# RPi-HAT_Conn-EE.net
KiCad netlist of a schematic drawn in Altium Designer
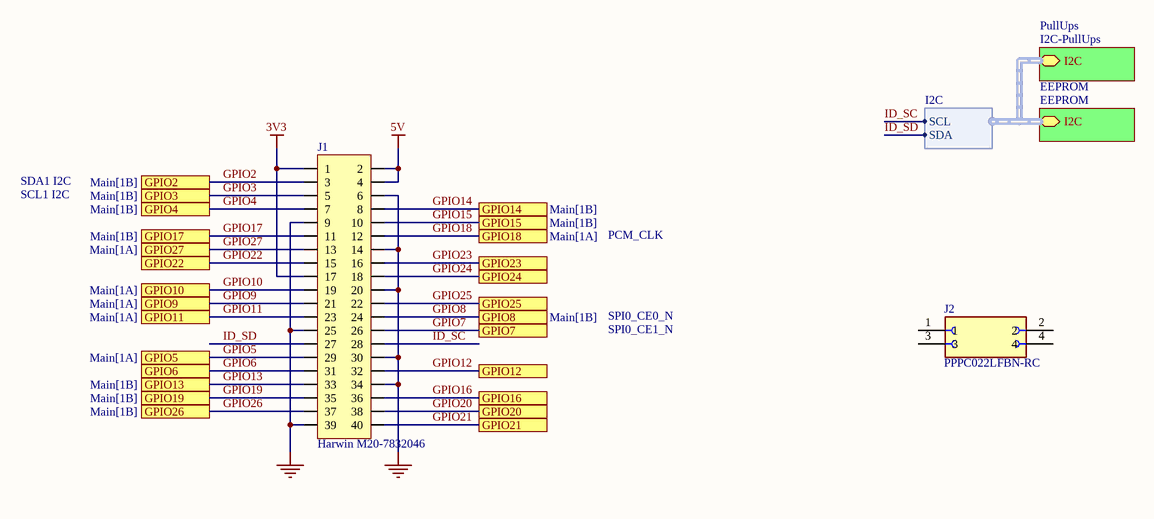
[diagram p0: RPi-HAT_Conn-EE.SchDoc]

(export (version "E")
  (design (tool "Eeschema 10.0.6"))
  (components
    (comp (ref "J1")
      (value "Harwin M20-7832046")
      (footprint "PCB-677180-1")
      (description "Headers & Wire Housings 20+20 DIL VERTICAL SOCKET TIN")
      (libsource (lib "CommunityVault") (part "CMP-2482621-3"))
    )
    (comp (ref "J2")
      (value "PPPC022LFBN-RC")
      (footprint "SULLINS_PPPC022LFBN-RC")
      (description "4 Position Header Connector 0.100 (2.54mm) Through Hole Gold")
      (fields (field (name "MF") "Sullins Connector Solutions"))
      (libsource (lib "Twill Technology Inc") (part "PPPC022LFBN-RC"))
    )
  )
  (nets
    (net (code "2") (name "/GPIO2") (class "Default")
      (node (ref "J1") (pin "3") (pinfunction "3_3") (pintype "passive"))
    )
    (net (code "3") (name "/GPIO3") (class "Default")
      (node (ref "J1") (pin "5") (pinfunction "5_5") (pintype "passive"))
    )
    (net (code "4") (name "/GPIO4") (class "Default")
      (node (ref "J1") (pin "7") (pinfunction "7_7") (pintype "passive"))
    )
    (net (code "5") (name "/GPIO5") (class "Default")
      (node (ref "J1") (pin "29") (pinfunction "29_29") (pintype "passive"))
    )
    (net (code "6") (name "/GPIO6") (class "Default")
      (node (ref "J1") (pin "31") (pinfunction "31_31") (pintype "passive"))
    )
    (net (code "7") (name "/GPIO7") (class "Default")
      (node (ref "J1") (pin "26") (pinfunction "26_26") (pintype "passive"))
    )
    (net (code "8") (name "/GPIO8") (class "Default")
      (node (ref "J1") (pin "24") (pinfunction "24_24") (pintype "passive"))
    )
    (net (code "9") (name "/GPIO9") (class "Default")
      (node (ref "J1") (pin "21") (pinfunction "21_21") (pintype "passive"))
    )
    (net (code "10") (name "/GPIO10") (class "Default")
      (node (ref "J1") (pin "19") (pinfunction "19_19") (pintype "passive"))
    )
    (net (code "11") (name "/GPIO11") (class "Default")
      (node (ref "J1") (pin "23") (pinfunction "23_23") (pintype "passive"))
    )
    (net (code "12") (name "/GPIO12") (class "Default")
      (node (ref "J1") (pin "32") (pinfunction "32_32") (pintype "passive"))
    )
    (net (code "13") (name "/GPIO13") (class "Default")
      (node (ref "J1") (pin "33") (pinfunction "33_33") (pintype "passive"))
    )
    (net (code "14") (name "/GPIO14") (class "Default")
      (node (ref "J1") (pin "8") (pinfunction "8_8") (pintype "passive"))
    )
    (net (code "15") (name "/GPIO15") (class "Default")
      (node (ref "J1") (pin "10") (pinfunction "10_10") (pintype "passive"))
    )
    (net (code "16") (name "/GPIO16") (class "Default")
      (node (ref "J1") (pin "36") (pinfunction "36_36") (pintype "passive"))
    )
    (net (code "17") (name "/GPIO17") (class "Default")
      (node (ref "J1") (pin "11") (pinfunction "11_11") (pintype "passive"))
    )
    (net (code "18") (name "/GPIO18") (class "Default")
      (node (ref "J1") (pin "12") (pinfunction "12_12") (pintype "passive"))
    )
    (net (code "19") (name "/GPIO19") (class "Default")
      (node (ref "J1") (pin "35") (pinfunction "35_35") (pintype "passive"))
    )
    (net (code "20") (name "/GPIO20") (class "Default")
      (node (ref "J1") (pin "38") (pinfunction "38_38") (pintype "passive"))
    )
    (net (code "21") (name "/GPIO21") (class "Default")
      (node (ref "J1") (pin "40") (pinfunction "40_40") (pintype "passive"))
    )
    (net (code "22") (name "/GPIO22") (class "Default")
      (node (ref "J1") (pin "15") (pinfunction "15_15") (pintype "passive"))
    )
    (net (code "23") (name "/GPIO23") (class "Default")
      (node (ref "J1") (pin "16") (pinfunction "16_16") (pintype "passive"))
    )
    (net (code "24") (name "/GPIO24") (class "Default")
      (node (ref "J1") (pin "18") (pinfunction "18_18") (pintype "passive"))
    )
    (net (code "25") (name "/GPIO25") (class "Default")
      (node (ref "J1") (pin "22") (pinfunction "22_22") (pintype "passive"))
    )
    (net (code "26") (name "/GPIO26") (class "Default")
      (node (ref "J1") (pin "37") (pinfunction "37_37") (pintype "passive"))
    )
    (net (code "27") (name "/GPIO27") (class "Default")
      (node (ref "J1") (pin "13") (pinfunction "13_13") (pintype "passive"))
    )
    (net (code "28") (name "/ID_SC") (class "Default")
      (node (ref "J1") (pin "28") (pinfunction "28_28") (pintype "passive"))
    )
    (net (code "29") (name "/ID_SD") (class "Default")
      (node (ref "J1") (pin "27") (pinfunction "27_27") (pintype "passive"))
    )
    (net (code "31") (name "3V3") (class "Default")
      (node (ref "J1") (pin "1") (pinfunction "1_1") (pintype "passive"))
      (node (ref "J1") (pin "17") (pinfunction "17_17") (pintype "passive"))
    )
    (net (code "32") (name "5V") (class "Default")
      (node (ref "J1") (pin "2") (pinfunction "2_2") (pintype "passive"))
      (node (ref "J1") (pin "4") (pinfunction "4_4") (pintype "passive"))
    )
    (net (code "33") (name "GND") (class "Default")
      (node (ref "J1") (pin "14") (pinfunction "14_14") (pintype "passive"))
      (node (ref "J1") (pin "20") (pinfunction "20_20") (pintype "passive"))
      (node (ref "J1") (pin "25") (pinfunction "25_25") (pintype "passive"))
      (node (ref "J1") (pin "30") (pinfunction "30_30") (pintype "passive"))
      (node (ref "J1") (pin "34") (pinfunction "34_34") (pintype "passive"))
      (node (ref "J1") (pin "39") (pinfunction "39_39") (pintype "passive"))
      (node (ref "J1") (pin "6") (pinfunction "6_6") (pintype "passive"))
      (node (ref "J1") (pin "9") (pinfunction "9_9") (pintype "passive"))
    )
    (net (code "34") (name "unconnected-(J2-Pad1)") (class "Default")
      (node (ref "J2") (pin "1") (pinfunction "1_1") (pintype "passive"))
    )
    (net (code "35") (name "unconnected-(J2-Pad2)") (class "Default")
      (node (ref "J2") (pin "2") (pinfunction "2_2") (pintype "passive"))
    )
    (net (code "36") (name "unconnected-(J2-Pad3)") (class "Default")
      (node (ref "J2") (pin "3") (pinfunction "3_3") (pintype "passive"))
    )
    (net (code "37") (name "unconnected-(J2-Pad4)") (class "Default")
      (node (ref "J2") (pin "4") (pinfunction "4_4") (pintype "passive"))
    )
  )
)
